# Face_PCB_Micro___Status_LEDs.net
KiCad netlist of a schematic drawn in Altium Designer
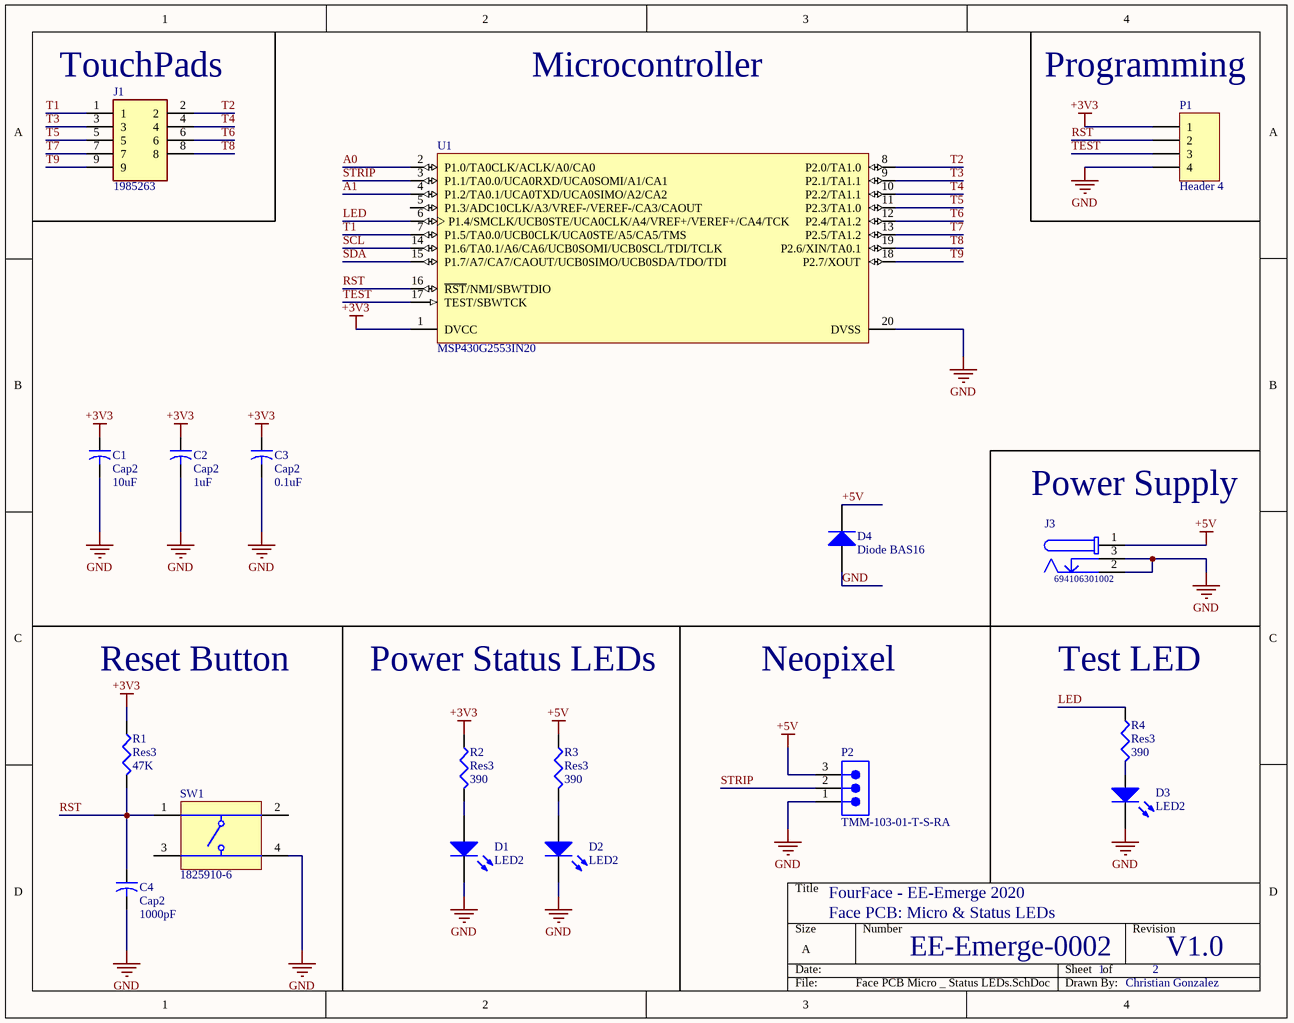
[diagram p0: Face PCB Micro _ Status LEDs.SchDoc]

(export (version "E")
  (design (tool "Eeschema 10.0.6"))
  (components
    (comp (ref "C1")
      (value "Cap2")
      (footprint "C0805")
      (description "Capacitor")
      (fields (field (name "ALTIUM_VALUE") "10uF") (field (name "PUBLISHER") "Altium Limited"))
      (libsource (lib "EE_Emerge_SkillsProject") (part "Cap2"))
    )
    (comp (ref "C2")
      (value "Cap2")
      (footprint "C0805")
      (description "Capacitor")
      (fields (field (name "ALTIUM_VALUE") "1uF") (field (name "PUBLISHER") "Altium Limited"))
      (libsource (lib "EE_Emerge_SkillsProject") (part "Cap2_4"))
    )
    (comp (ref "C3")
      (value "Cap2")
      (footprint "C0805")
      (description "Capacitor")
      (fields (field (name "ALTIUM_VALUE") "0.1uF") (field (name "PUBLISHER") "Altium Limited"))
      (libsource (lib "EE_Emerge_SkillsProject") (part "Cap2"))
    )
    (comp (ref "C4")
      (value "Cap2")
      (footprint "C0805")
      (description "Capacitor")
      (fields (field (name "ALTIUM_VALUE") "1000pF") (field (name "PUBLISHER") "Altium Limited"))
      (libsource (lib "EE_Emerge_SkillsProject") (part "Cap2"))
    )
    (comp (ref "D1")
      (value "LED2")
      (footprint "3.2X1.6X1.1")
      (description "Typical RED, GREEN, YELLOW, AMBER GaAs LED")
      (fields (field (name "PUBLISHER") "Altium Limited"))
      (libsource (lib "PCB_Project_2") (part "LED2"))
    )
    (comp (ref "D2")
      (value "LED2")
      (footprint "3.2X1.6X1.1")
      (description "Typical RED, GREEN, YELLOW, AMBER GaAs LED")
      (fields (field (name "PUBLISHER") "Altium Limited"))
      (libsource (lib "PCB_Project_2") (part "LED2"))
    )
    (comp (ref "D3")
      (value "LED2")
      (footprint "3.2X1.6X1.1")
      (description "Typical RED, GREEN, YELLOW, AMBER GaAs LED")
      (fields (field (name "PUBLISHER") "Altium Limited"))
      (libsource (lib "PCB_Project_2") (part "LED2"))
    )
    (comp (ref "D4")
      (value "Diode BAS16")
      (footprint "SOT-23_N")
      (description "Silicon Switching Diode for High-Speed Switching")
      (fields (field (name "PUBLISHER") "Altium Limited"))
      (libsource (lib "Miscellaneous Devices") (part "Diode BAS16"))
    )
    (comp (ref "J1")
      (value "1985263")
      (footprint "SamacSys:1985263")
      (description "Connector")
      (fields (field (name "MOUSER PART NUMBER") "651-1985263") (field (name "RS PART NUMBER") "6482559"))
      (libsource (lib "*") (part "1985263"))
    )
    (comp (ref "J3")
      (value "694106301002")
      (footprint "694106301002")
      (description "DC Power Jack Connector WR-DC, Male, Right Angled, THT, 5 A, 24 V")
      (fields (field (name "MANUFACTURER") "Wurth Elektronik") (field (name "PUBLISHER") "WurthElektronik"))
      (libsource (lib "Altium Content Vault") (part "WE-JACK-2CD3-RN"))
    )
    (comp (ref "P1")
      (value "Header 4")
      (footprint "HDR1X4")
      (description "Header, 4-Pin")
      (fields (field (name "PUBLISHER") "Altium Limited"))
      (libsource (lib "Miscellaneous Connectors") (part "Header 4"))
    )
    (comp (ref "P2")
      (value "TMM-103-01-T-S-RA")
      (footprint "SMTC-TMM-103-01-X-S-RA")
      (description "Low Profile Through-Hole Header, Right Angle, -55 to 105 degC, 2 mm Pitch, 3-Pin, Male, RoHS")
      (fields (field (name "MANUFACTURER") "Samtec"))
      (libsource (lib "PCB_Project_2") (part "CMP-1029-00176-1"))
    )
    (comp (ref "R1")
      (value "Res3")
      (footprint "6-0805_N")
      (description "Resistor")
      (fields (field (name "ALTIUM_VALUE") "47K") (field (name "PUBLISHER") "Altium Limited"))
      (libsource (lib "EE_Emerge_SkillsProject") (part "Res3"))
    )
    (comp (ref "R2")
      (value "Res3")
      (footprint "6-0805_N")
      (description "Resistor")
      (fields (field (name "ALTIUM_VALUE") "390") (field (name "PUBLISHER") "Altium Limited"))
      (libsource (lib "EE_Emerge_SkillsProject") (part "Res3"))
    )
    (comp (ref "R3")
      (value "Res3")
      (footprint "6-0805_N")
      (description "Resistor")
      (fields (field (name "ALTIUM_VALUE") "390") (field (name "PUBLISHER") "Altium Limited"))
      (libsource (lib "EE_Emerge_SkillsProject") (part "Res3"))
    )
    (comp (ref "R4")
      (value "Res3")
      (footprint "6-0805_N")
      (description "Resistor")
      (fields (field (name "ALTIUM_VALUE") "390") (field (name "PUBLISHER") "Altium Limited"))
      (libsource (lib "EE_Emerge_SkillsProject") (part "Res3"))
    )
    (comp (ref "SW1")
      (value "1825910-6")
      (footprint "TECO-1825910-6_V")
      (description "Tact Switch, SPST-NO, 0.05 A, -35 to 85 degC, 4-Pin THD, RoHS, Bulk")
      (fields (field (name "MANUFACTURER") "TE Connectivity"))
      (libsource (lib "Altium Content Vault") (part "SW-SPST-4_A"))
    )
    (comp (ref "U1")
      (value "MSP430G2553IN20")
      (footprint "N0020A")
      (fields (field (name "MANUFACTURER") "Texas Instruments"))
      (libsource (lib "PCB_Project_2") (part "CMP-0365-00184-2"))
    )
  )
  (nets
    (net (code "1") (name "+3V3") (class "Default")
      (node (ref "C1") (pin "1") (pinfunction "1_1") (pintype "passive"))
      (node (ref "C2") (pin "1") (pinfunction "1_1") (pintype "passive"))
      (node (ref "C3") (pin "1") (pinfunction "1_1") (pintype "passive"))
      (node (ref "P1") (pin "1") (pinfunction "1_1") (pintype "passive"))
      (node (ref "R1") (pin "1") (pinfunction "1_1") (pintype "passive"))
      (node (ref "R2") (pin "1") (pinfunction "1_1") (pintype "passive"))
      (node (ref "U1") (pin "1") (pinfunction "DVCC_1") (pintype "power_in"))
    )
    (net (code "2") (name "+5V") (class "Default")
      (node (ref "D4") (pin "3") (pinfunction "K_3") (pintype "passive"))
      (node (ref "J3") (pin "1") (pinfunction "1_1") (pintype "passive"))
      (node (ref "P2") (pin "3") (pinfunction "3_3") (pintype "passive"))
      (node (ref "R3") (pin "1") (pinfunction "1_1") (pintype "passive"))
    )
    (net (code "3") (name "/A0") (class "Default")
      (node (ref "U1") (pin "2") (pinfunction "P1.0/TA0CLK/ACLK/A0/CA0_2") (pintype "bidirectional"))
    )
    (net (code "4") (name "/A1") (class "Default")
      (node (ref "U1") (pin "4") (pinfunction "P1.2/TA0.1/UCA0TXD/UCA0SIMO/A2/CA2_4") (pintype "bidirectional"))
    )
    (net (code "5") (name "/LED") (class "Default")
      (node (ref "R4") (pin "1") (pinfunction "1_1") (pintype "passive"))
      (node (ref "U1") (pin "6") (pinfunction "P1.4/SMCLK/UCB0STE/UCA0CLK/A4/VREF+/VEREF+/CA4/TCK_6") (pintype "bidirectional"))
    )
    (net (code "6") (name "/RST") (class "Default")
      (node (ref "C4") (pin "1") (pinfunction "1_1") (pintype "passive"))
      (node (ref "P1") (pin "2") (pinfunction "2_2") (pintype "passive"))
      (node (ref "R1") (pin "2") (pinfunction "2_2") (pintype "passive"))
      (node (ref "SW1") (pin "1") (pinfunction "1_1") (pintype "passive"))
      (node (ref "U1") (pin "16") (pinfunction "~{RST}/NMI/SBWTDIO_16") (pintype "bidirectional"))
    )
    (net (code "7") (name "/SCL") (class "Default")
      (node (ref "U1") (pin "14") (pinfunction "P1.6/TA0.1/A6/CA6/UCB0SOMI/UCB0SCL/TDI/TCLK_14") (pintype "bidirectional"))
    )
    (net (code "8") (name "/SDA") (class "Default")
      (node (ref "U1") (pin "15") (pinfunction "P1.7/A7/CA7/CAOUT/UCB0SIMO/UCB0SDA/TDO/TDI_15") (pintype "bidirectional"))
    )
    (net (code "9") (name "/STRIP") (class "Default")
      (node (ref "P2") (pin "2") (pinfunction "2_2") (pintype "passive"))
      (node (ref "U1") (pin "3") (pinfunction "P1.1/TA0.0/UCA0RXD/UCA0SOMI/A1/CA1_3") (pintype "bidirectional"))
    )
    (net (code "10") (name "/T1") (class "Default")
      (node (ref "J1") (pin "1") (pinfunction "1_1") (pintype "passive"))
      (node (ref "U1") (pin "7") (pinfunction "P1.5/TA0.0/UCB0CLK/UCA0STE/A5/CA5/TMS_7") (pintype "bidirectional"))
    )
    (net (code "11") (name "/T2") (class "Default")
      (node (ref "J1") (pin "2") (pinfunction "2_2") (pintype "passive"))
      (node (ref "U1") (pin "8") (pinfunction "P2.0/TA1.0_8") (pintype "bidirectional"))
    )
    (net (code "12") (name "/T3") (class "Default")
      (node (ref "J1") (pin "3") (pinfunction "3_3") (pintype "passive"))
      (node (ref "U1") (pin "9") (pinfunction "P2.1/TA1.1_9") (pintype "bidirectional"))
    )
    (net (code "13") (name "/T4") (class "Default")
      (node (ref "J1") (pin "4") (pinfunction "4_4") (pintype "passive"))
      (node (ref "U1") (pin "10") (pinfunction "P2.2/TA1.1_10") (pintype "bidirectional"))
    )
    (net (code "14") (name "/T5") (class "Default")
      (node (ref "J1") (pin "5") (pinfunction "5_5") (pintype "passive"))
      (node (ref "U1") (pin "11") (pinfunction "P2.3/TA1.0_11") (pintype "bidirectional"))
    )
    (net (code "15") (name "/T6") (class "Default")
      (node (ref "J1") (pin "6") (pinfunction "6_6") (pintype "passive"))
      (node (ref "U1") (pin "12") (pinfunction "P2.4/TA1.2_12") (pintype "bidirectional"))
    )
    (net (code "16") (name "/T7") (class "Default")
      (node (ref "J1") (pin "7") (pinfunction "7_7") (pintype "passive"))
      (node (ref "U1") (pin "13") (pinfunction "P2.5/TA1.2_13") (pintype "bidirectional"))
    )
    (net (code "17") (name "/T8") (class "Default")
      (node (ref "J1") (pin "8") (pinfunction "8_8") (pintype "passive"))
      (node (ref "U1") (pin "19") (pinfunction "P2.6/XIN/TA0.1_19") (pintype "bidirectional"))
    )
    (net (code "18") (name "/T9") (class "Default")
      (node (ref "J1") (pin "9") (pinfunction "9_9") (pintype "passive"))
      (node (ref "U1") (pin "18") (pinfunction "P2.7/XOUT_18") (pintype "bidirectional"))
    )
    (net (code "19") (name "/TEST") (class "Default")
      (node (ref "P1") (pin "3") (pinfunction "3_3") (pintype "passive"))
      (node (ref "U1") (pin "17") (pinfunction "TEST/SBWTCK_17") (pintype "input"))
    )
    (net (code "20") (name "GND") (class "Default")
      (node (ref "C1") (pin "2") (pinfunction "2_2") (pintype "passive"))
      (node (ref "C2") (pin "2") (pinfunction "2_2") (pintype "passive"))
      (node (ref "C3") (pin "2") (pinfunction "2_2") (pintype "passive"))
      (node (ref "C4") (pin "2") (pinfunction "2_2") (pintype "passive"))
      (node (ref "D1") (pin "2") (pinfunction "K_2") (pintype "passive"))
      (node (ref "D2") (pin "2") (pinfunction "K_2") (pintype "passive"))
      (node (ref "D3") (pin "2") (pinfunction "K_2") (pintype "passive"))
      (node (ref "D4") (pin "1") (pinfunction "A_1") (pintype "passive"))
      (node (ref "J3") (pin "2") (pinfunction "2_2") (pintype "passive"))
      (node (ref "J3") (pin "3") (pinfunction "3_3") (pintype "passive"))
      (node (ref "P1") (pin "4") (pinfunction "4_4") (pintype "passive"))
      (node (ref "P2") (pin "1") (pinfunction "1_1") (pintype "passive"))
      (node (ref "SW1") (pin "4") (pinfunction "4_4") (pintype "passive"))
      (node (ref "U1") (pin "20") (pinfunction "DVSS_20") (pintype "power_in"))
    )
    (net (code "21") (name "Net-(D1-A)") (class "Default")
      (node (ref "D1") (pin "1") (pinfunction "A_1") (pintype "passive"))
      (node (ref "R2") (pin "2") (pinfunction "2_2") (pintype "passive"))
    )
    (net (code "22") (name "Net-(D2-A)") (class "Default")
      (node (ref "D2") (pin "1") (pinfunction "A_1") (pintype "passive"))
      (node (ref "R3") (pin "2") (pinfunction "2_2") (pintype "passive"))
    )
    (net (code "23") (name "Net-(D3-A)") (class "Default")
      (node (ref "D3") (pin "1") (pinfunction "A_1") (pintype "passive"))
      (node (ref "R4") (pin "2") (pinfunction "2_2") (pintype "passive"))
    )
    (net (code "24") (name "unconnected-(SW1-Pad2)") (class "Default")
      (node (ref "SW1") (pin "2") (pinfunction "2_2") (pintype "passive"))
    )
    (net (code "25") (name "unconnected-(SW1-Pad3)") (class "Default")
      (node (ref "SW1") (pin "3") (pinfunction "3_3") (pintype "passive"))
    )
    (net (code "26") (name "unconnected-(U1-P1.3{slash}ADC10CLK{slash}A3{slash}VREF-{slash}VEREF-{slash}CA3{slash}CAOUT-Pad5)") (class "Default")
      (node (ref "U1") (pin "5") (pinfunction "P1.3/ADC10CLK/A3/VREF-/VEREF-/CA3/CAOUT_5") (pintype "bidirectional"))
    )
  )
)
